# battery-charger.net
KiCad netlist of a schematic drawn in EAGLE
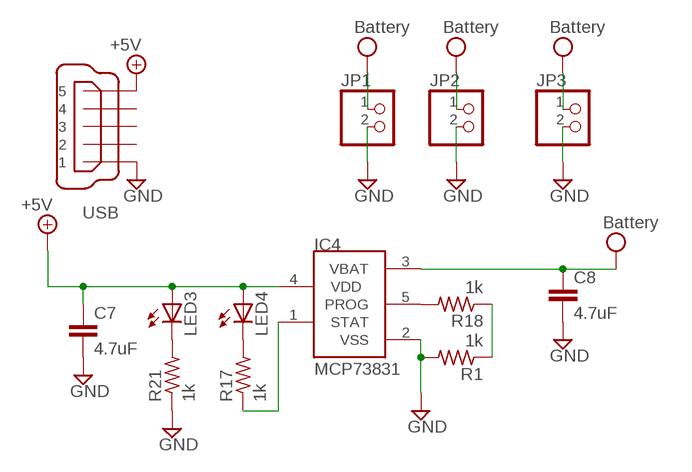
[diagram p0: schematic, sheet 1]

(export (version "E")
  (design (tool "Eeschema 10.0.6"))
  (components
    (comp (ref "C7")
      (value "4.7uF")
      (footprint "eagle-import:C025-024X044")
      (libsource (lib "eagle-import") (part "C-EU025-024X044"))
    )
    (comp (ref "C8")
      (value "4.7uF")
      (footprint "eagle-import:C025-024X044")
      (libsource (lib "eagle-import") (part "C-EU025-024X044"))
    )
    (comp (ref "IC4")
      (value "MCP73831")
      (footprint "eagle-import:SOT23-5L")
      (libsource (lib "eagle-import") (part "MCP73831"))
    )
    (comp (ref "JP1")
      (value "PINHD-1X2")
      (footprint "eagle-import:1X02")
      (libsource (lib "eagle-import") (part "PINHD-1X2"))
    )
    (comp (ref "JP2")
      (value "PINHD-1X2")
      (footprint "eagle-import:1X02")
      (libsource (lib "eagle-import") (part "PINHD-1X2"))
    )
    (comp (ref "JP3")
      (value "PINHD-1X2")
      (footprint "eagle-import:1X02")
      (libsource (lib "eagle-import") (part "PINHD-1X2"))
    )
    (comp (ref "LED3")
      (value "LED3MM")
      (footprint "eagle-import:LED3MM")
      (libsource (lib "eagle-import") (part "LED3MM"))
    )
    (comp (ref "LED4")
      (value "LED3MM")
      (footprint "eagle-import:LED3MM")
      (libsource (lib "eagle-import") (part "LED3MM"))
    )
    (comp (ref "R1")
      (value "1k")
      (footprint "eagle-import:MINI_MELF-0204R")
      (libsource (lib "eagle-import") (part "R-US_MELF0204R"))
    )
    (comp (ref "R17")
      (value "1k")
      (footprint "eagle-import:MINI_MELF-0204R")
      (libsource (lib "eagle-import") (part "R-US_MELF0204R"))
    )
    (comp (ref "R18")
      (value "1k")
      (footprint "eagle-import:MINI_MELF-0204R")
      (libsource (lib "eagle-import") (part "R-US_MELF0204R"))
    )
    (comp (ref "R21")
      (value "1k")
      (footprint "eagle-import:MINI_MELF-0204R")
      (libsource (lib "eagle-import") (part "R-US_MELF0204R"))
    )
    (comp (ref "USB")
      (value "MICRO-USB-ZX62R-B-5P")
      (footprint "eagle-import:ZX62R-B-5P")
      (libsource (lib "eagle-import") (part "MICRO-USB-ZX62R-B-5P"))
    )
  )
  (nets
    (net (code "1") (name "+5V") (class "Default")
      (node (ref "C7") (pin "1") (pinfunction "1_1") (pintype "passive"))
      (node (ref "IC4") (pin "4") (pinfunction "VDD_4") (pintype "bidirectional"))
      (node (ref "LED3") (pin "A") (pinfunction "A_A") (pintype "passive"))
      (node (ref "LED4") (pin "A") (pinfunction "A_A") (pintype "passive"))
      (node (ref "USB") (pin "5") (pinfunction "5_5") (pintype "input"))
    )
    (net (code "2") (name "Battery") (class "Default")
      (node (ref "C8") (pin "1") (pinfunction "1_1") (pintype "passive"))
      (node (ref "IC4") (pin "3") (pinfunction "VBAT_3") (pintype "bidirectional"))
      (node (ref "JP1") (pin "1") (pinfunction "1_1") (pintype "passive"))
      (node (ref "JP2") (pin "1") (pinfunction "1_1") (pintype "passive"))
      (node (ref "JP3") (pin "1") (pinfunction "1_1") (pintype "passive"))
    )
    (net (code "3") (name "GND") (class "Default")
      (node (ref "C7") (pin "2") (pinfunction "2_2") (pintype "passive"))
      (node (ref "C8") (pin "2") (pinfunction "2_2") (pintype "passive"))
      (node (ref "IC4") (pin "2") (pinfunction "VSS_2") (pintype "bidirectional"))
      (node (ref "JP1") (pin "2") (pinfunction "2_2") (pintype "passive"))
      (node (ref "JP2") (pin "2") (pinfunction "2_2") (pintype "passive"))
      (node (ref "JP3") (pin "2") (pinfunction "2_2") (pintype "passive"))
      (node (ref "R1") (pin "2") (pinfunction "2_2") (pintype "passive"))
      (node (ref "R21") (pin "1") (pinfunction "1_1") (pintype "passive"))
      (node (ref "USB") (pin "1") (pinfunction "1_1") (pintype "input"))
    )
    (net (code "4") (name "Net-(IC4-PROG)") (class "Default")
      (node (ref "IC4") (pin "5") (pinfunction "PROG_5") (pintype "bidirectional"))
      (node (ref "R18") (pin "2") (pinfunction "2_2") (pintype "passive"))
    )
    (net (code "5") (name "Net-(IC4-STAT)") (class "Default")
      (node (ref "IC4") (pin "1") (pinfunction "STAT_1") (pintype "bidirectional"))
      (node (ref "R17") (pin "1") (pinfunction "1_1") (pintype "passive"))
    )
    (net (code "6") (name "Net-(LED3-C)") (class "Default")
      (node (ref "LED3") (pin "K") (pinfunction "C_K") (pintype "passive"))
      (node (ref "R21") (pin "2") (pinfunction "2_2") (pintype "passive"))
    )
    (net (code "7") (name "Net-(LED4-C)") (class "Default")
      (node (ref "LED4") (pin "K") (pinfunction "C_K") (pintype "passive"))
      (node (ref "R17") (pin "2") (pinfunction "2_2") (pintype "passive"))
    )
    (net (code "8") (name "Net-(R1-Pad1)") (class "Default")
      (node (ref "R1") (pin "1") (pinfunction "1_1") (pintype "passive"))
      (node (ref "R18") (pin "1") (pinfunction "1_1") (pintype "passive"))
    )
    (net (code "9") (name "unconnected-(USB-Pad2)") (class "Default")
      (node (ref "USB") (pin "2") (pinfunction "2_2") (pintype "input"))
    )
    (net (code "10") (name "unconnected-(USB-Pad3)") (class "Default")
      (node (ref "USB") (pin "3") (pinfunction "3_3") (pintype "input"))
    )
    (net (code "11") (name "unconnected-(USB-Pad4)") (class "Default")
      (node (ref "USB") (pin "4") (pinfunction "4_4") (pintype "input"))
    )
  )
)
